# MCU.net
KiCad netlist of a schematic drawn in Altium Designer
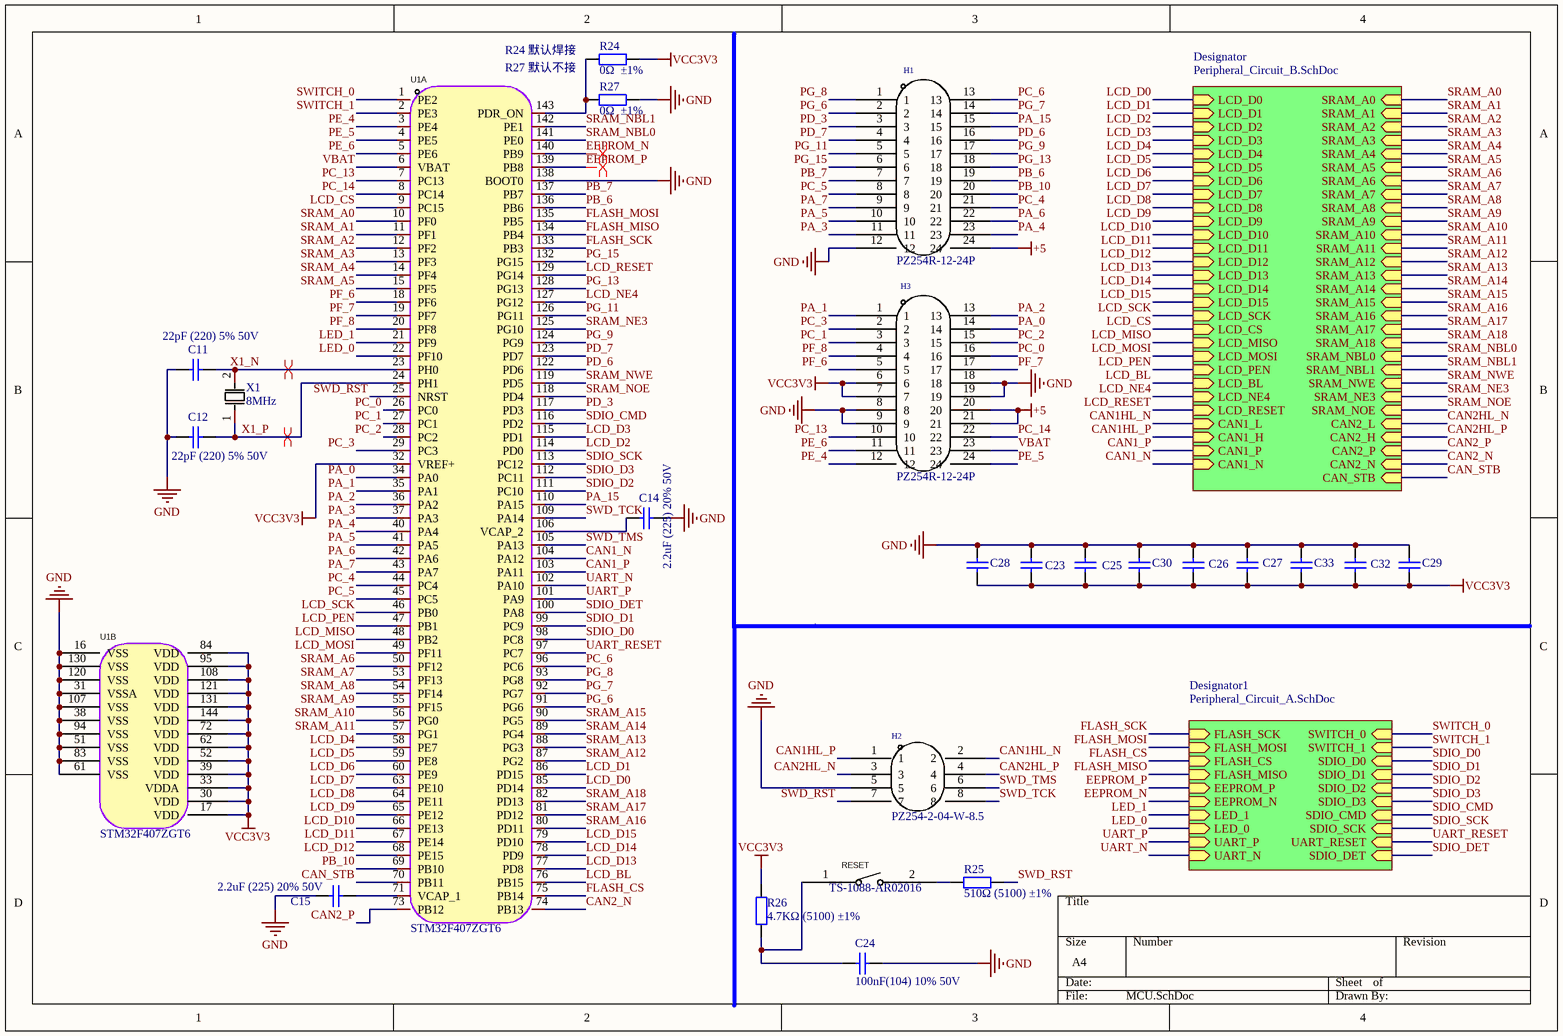
[diagram p0: MCU.SchDoc]

(export (version "E")
  (design (tool "Eeschema 10.0.6"))
  (components
    (comp (ref "C11")
      (value "22pF (220) 5% 50V")
      (footprint "0805_C")
      (description "贴片电容")
      (libsource (lib "Miscellaneous Devices LC") (part "0805 22pF (220) 5% 50V"))
    )
    (comp (ref "C12")
      (value "22pF (220) 5% 50V")
      (footprint "0805_C")
      (description "贴片电容")
      (libsource (lib "Miscellaneous Devices LC") (part "0805 22pF (220) 5% 50V"))
    )
    (comp (ref "C14")
      (value "2.2uF (225) 20% 50V")
      (footprint "0805_C")
      (description "贴片电容")
      (libsource (lib "Miscellaneous Devices LC") (part "0805 2.2uF (225) 20% 50V"))
    )
    (comp (ref "C15")
      (value "2.2uF (225) 20% 50V")
      (footprint "0805_C")
      (description "贴片电容")
      (libsource (lib "Miscellaneous Devices LC") (part "0805 2.2uF (225) 20% 50V"))
    )
    (comp (ref "C23")
      (value "100nF(104) 10% 50V")
      (footprint "0805_C")
      (description "贴片电容")
      (libsource (lib "Miscellaneous Devices LC") (part "0805 100nF(104) 10% 50V"))
    )
    (comp (ref "C24")
      (value "100nF(104) 10% 50V")
      (footprint "0805_C")
      (description "贴片电容")
      (libsource (lib "Miscellaneous Devices LC") (part "0805 100nF(104) 10% 50V"))
    )
    (comp (ref "C25")
      (value "100nF(104) 10% 50V")
      (footprint "0805_C")
      (description "贴片电容")
      (libsource (lib "Miscellaneous Devices LC") (part "0805 100nF(104) 10% 50V"))
    )
    (comp (ref "C26")
      (value "100nF(104) 10% 50V")
      (footprint "0805_C")
      (description "贴片电容")
      (libsource (lib "Miscellaneous Devices LC") (part "0805 100nF(104) 10% 50V"))
    )
    (comp (ref "C27")
      (value "100nF(104) 10% 50V")
      (footprint "0805_C")
      (description "贴片电容")
      (libsource (lib "Miscellaneous Devices LC") (part "0805 100nF(104) 10% 50V"))
    )
    (comp (ref "C28")
      (value "100nF(104) 10% 50V")
      (footprint "0805_C")
      (description "贴片电容")
      (libsource (lib "Miscellaneous Devices LC") (part "0805 100nF(104) 10% 50V"))
    )
    (comp (ref "C29")
      (value "100nF(104) 10% 50V")
      (footprint "0805_C")
      (description "贴片电容")
      (libsource (lib "Miscellaneous Devices LC") (part "0805 100nF(104) 10% 50V"))
    )
    (comp (ref "C30")
      (value "100nF(104) 10% 50V")
      (footprint "0805_C")
      (description "贴片电容")
      (libsource (lib "Miscellaneous Devices LC") (part "0805 100nF(104) 10% 50V"))
    )
    (comp (ref "C32")
      (value "100nF(104) 10% 50V")
      (footprint "0805_C")
      (description "贴片电容")
      (libsource (lib "Miscellaneous Devices LC") (part "0805 100nF(104) 10% 50V"))
    )
    (comp (ref "C33")
      (value "100nF(104) 10% 50V")
      (footprint "0805_C")
      (description "贴片电容")
      (libsource (lib "Miscellaneous Devices LC") (part "0805 100nF(104) 10% 50V"))
    )
    (comp (ref "H1")
      (value "PZ254R-12-24P")
      (footprint "PZ254R-12-24P")
      (description "2X12P 弯针")
      (fields (field (name "MANUFACTURER") "XFCN(兴飞)") (field (name "NAME") "PZ254R-12-24P"))
      (libsource (lib "EXTRA") (part "PZ254R-12-24P"))
    )
    (comp (ref "H2")
      (value "PZ254-2-04-W-8.5")
      (footprint "PZ254-2-04-W-8.5")
      (description "2.54mm 2x4p 弯针")
      (fields (field (name "MANUFACTURER") "HCTL(华灿天禄)"))
      (libsource (lib "EXTRA") (part "PZ254-2-04-W-8.5"))
    )
    (comp (ref "H3")
      (value "PZ254R-12-24P")
      (footprint "PZ254R-12-24P")
      (description "2X12P 弯针")
      (fields (field (name "MANUFACTURER") "XFCN(兴飞)") (field (name "NAME") "PZ254R-12-24P"))
      (libsource (lib "EXTRA") (part "PZ254R-12-24P"))
    )
    (comp (ref "R24")
      (value "0Ω  ±1%")
      (footprint "0805_R")
      (description "贴片电阻")
      (libsource (lib "Miscellaneous Devices LC") (part "0805 510Ω (5100) 1%"))
    )
    (comp (ref "R25")
      (value "510Ω (5100) ±1%")
      (footprint "0805_R")
      (description "贴片电阻")
      (libsource (lib "Miscellaneous Devices LC") (part "0805 510Ω (5100) 1%"))
    )
    (comp (ref "R26")
      (value "4.7KΩ (5100) ±1%")
      (footprint "0805_R")
      (description "贴片电阻")
      (libsource (lib "") (part "0805 510Ω (5100) 1%_1"))
    )
    (comp (ref "R27")
      (value "0Ω  ±1%")
      (footprint "0805_R")
      (description "贴片电阻")
      (libsource (lib "Miscellaneous Devices LC") (part "0805 510Ω (5100) 1%"))
    )
    (comp (ref "RESET")
      (value "TS-1088-AR02016")
      (footprint "SW-SMD_L3.9-W3.0-P4.45")
      (description "轻触开关")
      (fields (field (name "MANUFACTURER") "XUNPU(讯普)"))
      (libsource (lib "EXTRA") (part "TS-1088-AR02016"))
    )
    (comp (ref "U1")
      (value "STM32F407ZGT6")
      (footprint "LQFP-144_L20.0-W20.0-P0.50-LS22.0-BL")
      (description "STM32F407ZGT6MCU")
      (fields (field (name "MANUFACTURER") "ST(意法半导体)"))
      (libsource (lib "EXTRA") (part "STM32F407ZGT6"))
    )
    (comp (ref "X1")
      (value "8MHZ")
      (footprint "CRYSTAL-SMD_L5.0-W3.2")
      (description "贴片晶振")
      (fields
        (field (name "MANUFACTURER") "YXC(扬兴晶振)")
        (field (name "MANUFACTURER PART") "X50328MSB2GI")
        (field (name "NAME") "8MHz")
      )
      (libsource (lib "EXTRA") (part "X50328MSB2GI"))
    )
  )
  (nets
    (net (code "1") (name "+5") (class "Default")
      (node (ref "H1") (pin "24") (pinfunction "24_24") (pintype "passive"))
      (node (ref "H3") (pin "20") (pinfunction "20_20") (pintype "passive"))
      (node (ref "H3") (pin "21") (pinfunction "21_21") (pintype "passive"))
    )
    (net (code "2") (name "/CAN1HL_N") (class "Default")
      (node (ref "H2") (pin "2") (pinfunction "2_2") (pintype "passive"))
    )
    (net (code "3") (name "/CAN1HL_P") (class "Default")
      (node (ref "H2") (pin "1") (pinfunction "1_1") (pintype "passive"))
    )
    (net (code "4") (name "/CAN1_N") (class "Default")
      (node (ref "U1") (pin "104") (pinfunction "PA12_104") (pintype "passive"))
    )
    (net (code "5") (name "/CAN1_P") (class "Default")
      (node (ref "U1") (pin "103") (pinfunction "PA11_103") (pintype "passive"))
    )
    (net (code "6") (name "/CAN2HL_N") (class "Default")
      (node (ref "H2") (pin "3") (pinfunction "3_3") (pintype "passive"))
    )
    (net (code "7") (name "/CAN2HL_P") (class "Default")
      (node (ref "H2") (pin "4") (pinfunction "4_4") (pintype "passive"))
    )
    (net (code "8") (name "/CAN2_N") (class "Default")
      (node (ref "U1") (pin "74") (pinfunction "PB13_74") (pintype "passive"))
    )
    (net (code "9") (name "/CAN2_P") (class "Default")
      (node (ref "U1") (pin "73") (pinfunction "PB12_73") (pintype "passive"))
    )
    (net (code "10") (name "/CAN_STB") (class "Default")
      (node (ref "U1") (pin "70") (pinfunction "PB11_70") (pintype "passive"))
    )
    (net (code "11") (name "/EEPROM_N") (class "Default")
      (node (ref "U1") (pin "140") (pinfunction "PB9_140") (pintype "passive"))
    )
    (net (code "12") (name "/EEPROM_P") (class "Default")
      (node (ref "U1") (pin "139") (pinfunction "PB8_139") (pintype "passive"))
    )
    (net (code "13") (name "/FLASH_CS") (class "Default")
      (node (ref "U1") (pin "75") (pinfunction "PB14_75") (pintype "passive"))
    )
    (net (code "14") (name "/FLASH_MISO") (class "Default")
      (node (ref "U1") (pin "134") (pinfunction "PB4_134") (pintype "passive"))
    )
    (net (code "15") (name "/FLASH_MOSI") (class "Default")
      (node (ref "U1") (pin "135") (pinfunction "PB5_135") (pintype "passive"))
    )
    (net (code "16") (name "/FLASH_SCK") (class "Default")
      (node (ref "U1") (pin "133") (pinfunction "PB3_133") (pintype "passive"))
    )
    (net (code "17") (name "/LCD_BL") (class "Default")
      (node (ref "U1") (pin "76") (pinfunction "PB15_76") (pintype "passive"))
    )
    (net (code "18") (name "/LCD_CS") (class "Default")
      (node (ref "U1") (pin "9") (pinfunction "PC15_9") (pintype "passive"))
    )
    (net (code "19") (name "/LCD_D0") (class "Default")
      (node (ref "U1") (pin "85") (pinfunction "PD14_85") (pintype "passive"))
    )
    (net (code "20") (name "/LCD_D1") (class "Default")
      (node (ref "U1") (pin "86") (pinfunction "PD15_86") (pintype "passive"))
    )
    (net (code "21") (name "/LCD_D2") (class "Default")
      (node (ref "U1") (pin "114") (pinfunction "PD0_114") (pintype "passive"))
    )
    (net (code "22") (name "/LCD_D3") (class "Default")
      (node (ref "U1") (pin "115") (pinfunction "PD1_115") (pintype "passive"))
    )
    (net (code "23") (name "/LCD_D4") (class "Default")
      (node (ref "U1") (pin "58") (pinfunction "PE7_58") (pintype "passive"))
    )
    (net (code "24") (name "/LCD_D5") (class "Default")
      (node (ref "U1") (pin "59") (pinfunction "PE8_59") (pintype "passive"))
    )
    (net (code "25") (name "/LCD_D6") (class "Default")
      (node (ref "U1") (pin "60") (pinfunction "PE9_60") (pintype "passive"))
    )
    (net (code "26") (name "/LCD_D7") (class "Default")
      (node (ref "U1") (pin "63") (pinfunction "PE10_63") (pintype "passive"))
    )
    (net (code "27") (name "/LCD_D8") (class "Default")
      (node (ref "U1") (pin "64") (pinfunction "PE11_64") (pintype "passive"))
    )
    (net (code "28") (name "/LCD_D9") (class "Default")
      (node (ref "U1") (pin "65") (pinfunction "PE12_65") (pintype "passive"))
    )
    (net (code "29") (name "/LCD_D10") (class "Default")
      (node (ref "U1") (pin "66") (pinfunction "PE13_66") (pintype "passive"))
    )
    (net (code "30") (name "/LCD_D11") (class "Default")
      (node (ref "U1") (pin "67") (pinfunction "PE14_67") (pintype "passive"))
    )
    (net (code "31") (name "/LCD_D12") (class "Default")
      (node (ref "U1") (pin "68") (pinfunction "PE15_68") (pintype "passive"))
    )
    (net (code "32") (name "/LCD_D13") (class "Default")
      (node (ref "U1") (pin "77") (pinfunction "PD8_77") (pintype "passive"))
    )
    (net (code "33") (name "/LCD_D14") (class "Default")
      (node (ref "U1") (pin "78") (pinfunction "PD9_78") (pintype "passive"))
    )
    (net (code "34") (name "/LCD_D15") (class "Default")
      (node (ref "U1") (pin "79") (pinfunction "PD10_79") (pintype "passive"))
    )
    (net (code "35") (name "/LCD_MISO") (class "Default")
      (node (ref "U1") (pin "48") (pinfunction "PB2_48") (pintype "passive"))
    )
    (net (code "36") (name "/LCD_MOSI") (class "Default")
      (node (ref "U1") (pin "49") (pinfunction "PF11_49") (pintype "passive"))
    )
    (net (code "37") (name "/LCD_NE4") (class "Default")
      (node (ref "U1") (pin "127") (pinfunction "PG12_127") (pintype "passive"))
    )
    (net (code "38") (name "/LCD_PEN") (class "Default")
      (node (ref "U1") (pin "47") (pinfunction "PB1_47") (pintype "passive"))
    )
    (net (code "39") (name "/LCD_RESET") (class "Default")
      (node (ref "U1") (pin "129") (pinfunction "PG14_129") (pintype "passive"))
    )
    (net (code "40") (name "/LCD_SCK") (class "Default")
      (node (ref "U1") (pin "46") (pinfunction "PB0_46") (pintype "passive"))
    )
    (net (code "41") (name "/LED_0") (class "Default")
      (node (ref "U1") (pin "22") (pinfunction "PF10_22") (pintype "passive"))
    )
    (net (code "42") (name "/LED_1") (class "Default")
      (node (ref "U1") (pin "21") (pinfunction "PF9_21") (pintype "passive"))
    )
    (net (code "43") (name "/PA_0") (class "Default")
      (node (ref "H3") (pin "14") (pinfunction "14_14") (pintype "passive"))
      (node (ref "U1") (pin "34") (pinfunction "PA0_34") (pintype "passive"))
    )
    (net (code "44") (name "/PA_1") (class "Default")
      (node (ref "H3") (pin "1") (pinfunction "1_1") (pintype "passive"))
      (node (ref "U1") (pin "35") (pinfunction "PA1_35") (pintype "passive"))
    )
    (net (code "45") (name "/PA_2") (class "Default")
      (node (ref "H3") (pin "13") (pinfunction "13_13") (pintype "passive"))
      (node (ref "U1") (pin "36") (pinfunction "PA2_36") (pintype "passive"))
    )
    (net (code "46") (name "/PA_3") (class "Default")
      (node (ref "H1") (pin "11") (pinfunction "11_11") (pintype "passive"))
      (node (ref "U1") (pin "37") (pinfunction "PA3_37") (pintype "passive"))
    )
    (net (code "47") (name "/PA_4") (class "Default")
      (node (ref "H1") (pin "23") (pinfunction "23_23") (pintype "passive"))
      (node (ref "U1") (pin "40") (pinfunction "PA4_40") (pintype "passive"))
    )
    (net (code "48") (name "/PA_5") (class "Default")
      (node (ref "H1") (pin "10") (pinfunction "10_10") (pintype "passive"))
      (node (ref "U1") (pin "41") (pinfunction "PA5_41") (pintype "passive"))
    )
    (net (code "49") (name "/PA_6") (class "Default")
      (node (ref "H1") (pin "22") (pinfunction "22_22") (pintype "passive"))
      (node (ref "U1") (pin "42") (pinfunction "PA6_42") (pintype "passive"))
    )
    (net (code "50") (name "/PA_7") (class "Default")
      (node (ref "H1") (pin "9") (pinfunction "9_9") (pintype "passive"))
      (node (ref "U1") (pin "43") (pinfunction "PA7_43") (pintype "passive"))
    )
    (net (code "51") (name "/PA_15") (class "Default")
      (node (ref "H1") (pin "15") (pinfunction "15_15") (pintype "passive"))
      (node (ref "U1") (pin "110") (pinfunction "PA15_110") (pintype "passive"))
    )
    (net (code "52") (name "/PB_6") (class "Default")
      (node (ref "H1") (pin "19") (pinfunction "19_19") (pintype "passive"))
      (node (ref "U1") (pin "136") (pinfunction "PB6_136") (pintype "passive"))
    )
    (net (code "53") (name "/PB_7") (class "Default")
      (node (ref "H1") (pin "7") (pinfunction "7_7") (pintype "passive"))
      (node (ref "U1") (pin "137") (pinfunction "PB7_137") (pintype "passive"))
    )
    (net (code "54") (name "/PB_10") (class "Default")
      (node (ref "H1") (pin "20") (pinfunction "20_20") (pintype "passive"))
      (node (ref "U1") (pin "69") (pinfunction "PB10_69") (pintype "passive"))
    )
    (net (code "55") (name "/PC_0") (class "Default")
      (node (ref "H3") (pin "16") (pinfunction "16_16") (pintype "passive"))
      (node (ref "U1") (pin "26") (pinfunction "PC0_26") (pintype "passive"))
    )
    (net (code "56") (name "/PC_1") (class "Default")
      (node (ref "H3") (pin "3") (pinfunction "3_3") (pintype "passive"))
      (node (ref "U1") (pin "27") (pinfunction "PC1_27") (pintype "passive"))
    )
    (net (code "57") (name "/PC_2") (class "Default")
      (node (ref "H3") (pin "15") (pinfunction "15_15") (pintype "passive"))
      (node (ref "U1") (pin "28") (pinfunction "PC2_28") (pintype "passive"))
    )
    (net (code "58") (name "/PC_3") (class "Default")
      (node (ref "H3") (pin "2") (pinfunction "2_2") (pintype "passive"))
      (node (ref "U1") (pin "29") (pinfunction "PC3_29") (pintype "passive"))
    )
    (net (code "59") (name "/PC_4") (class "Default")
      (node (ref "H1") (pin "21") (pinfunction "21_21") (pintype "passive"))
      (node (ref "U1") (pin "44") (pinfunction "PC4_44") (pintype "passive"))
    )
    (net (code "60") (name "/PC_5") (class "Default")
      (node (ref "H1") (pin "8") (pinfunction "8_8") (pintype "passive"))
      (node (ref "U1") (pin "45") (pinfunction "PC5_45") (pintype "passive"))
    )
    (net (code "61") (name "/PC_6") (class "Default")
      (node (ref "H1") (pin "13") (pinfunction "13_13") (pintype "passive"))
      (node (ref "U1") (pin "96") (pinfunction "PC6_96") (pintype "passive"))
    )
    (net (code "62") (name "/PC_13") (class "Default")
      (node (ref "H3") (pin "10") (pinfunction "10_10") (pintype "passive"))
      (node (ref "U1") (pin "7") (pinfunction "PC13_7") (pintype "passive"))
    )
    (net (code "63") (name "/PC_14") (class "Default")
      (node (ref "H3") (pin "22") (pinfunction "22_22") (pintype "passive"))
      (node (ref "U1") (pin "8") (pinfunction "PC14_8") (pintype "passive"))
    )
    (net (code "64") (name "/PD_3") (class "Default")
      (node (ref "H1") (pin "3") (pinfunction "3_3") (pintype "passive"))
      (node (ref "U1") (pin "117") (pinfunction "PD3_117") (pintype "passive"))
    )
    (net (code "65") (name "/PD_6") (class "Default")
      (node (ref "H1") (pin "16") (pinfunction "16_16") (pintype "passive"))
      (node (ref "U1") (pin "122") (pinfunction "PD6_122") (pintype "passive"))
    )
    (net (code "66") (name "/PD_7") (class "Default")
      (node (ref "H1") (pin "4") (pinfunction "4_4") (pintype "passive"))
      (node (ref "U1") (pin "123") (pinfunction "PD7_123") (pintype "passive"))
    )
    (net (code "67") (name "/PE_4") (class "Default")
      (node (ref "H3") (pin "12") (pinfunction "12_12") (pintype "passive"))
      (node (ref "U1") (pin "3") (pinfunction "PE4_3") (pintype "passive"))
    )
    (net (code "68") (name "/PE_5") (class "Default")
      (node (ref "H3") (pin "24") (pinfunction "24_24") (pintype "passive"))
      (node (ref "U1") (pin "4") (pinfunction "PE5_4") (pintype "passive"))
    )
    (net (code "69") (name "/PE_6") (class "Default")
      (node (ref "H3") (pin "11") (pinfunction "11_11") (pintype "passive"))
      (node (ref "U1") (pin "5") (pinfunction "PE6_5") (pintype "passive"))
    )
    (net (code "70") (name "/PF_6") (class "Default")
      (node (ref "H3") (pin "5") (pinfunction "5_5") (pintype "passive"))
      (node (ref "U1") (pin "18") (pinfunction "PF6_18") (pintype "passive"))
    )
    (net (code "71") (name "/PF_7") (class "Default")
      (node (ref "H3") (pin "17") (pinfunction "17_17") (pintype "passive"))
      (node (ref "U1") (pin "19") (pinfunction "PF7_19") (pintype "passive"))
    )
    (net (code "72") (name "/PF_8") (class "Default")
      (node (ref "H3") (pin "4") (pinfunction "4_4") (pintype "passive"))
      (node (ref "U1") (pin "20") (pinfunction "PF8_20") (pintype "passive"))
    )
    (net (code "73") (name "/PG_6") (class "Default")
      (node (ref "H1") (pin "2") (pinfunction "2_2") (pintype "passive"))
      (node (ref "U1") (pin "91") (pinfunction "PG6_91") (pintype "passive"))
    )
    (net (code "74") (name "/PG_7") (class "Default")
      (node (ref "H1") (pin "14") (pinfunction "14_14") (pintype "passive"))
      (node (ref "U1") (pin "92") (pinfunction "PG7_92") (pintype "passive"))
    )
    (net (code "75") (name "/PG_8") (class "Default")
      (node (ref "H1") (pin "1") (pinfunction "1_1") (pintype "passive"))
      (node (ref "U1") (pin "93") (pinfunction "PG8_93") (pintype "passive"))
    )
    (net (code "76") (name "/PG_9") (class "Default")
      (node (ref "H1") (pin "17") (pinfunction "17_17") (pintype "passive"))
      (node (ref "U1") (pin "124") (pinfunction "PG9_124") (pintype "passive"))
    )
    (net (code "77") (name "/PG_11") (class "Default")
      (node (ref "H1") (pin "5") (pinfunction "5_5") (pintype "passive"))
      (node (ref "U1") (pin "126") (pinfunction "PG11_126") (pintype "passive"))
    )
    (net (code "78") (name "/PG_13") (class "Default")
      (node (ref "H1") (pin "18") (pinfunction "18_18") (pintype "passive"))
      (node (ref "U1") (pin "128") (pinfunction "PG13_128") (pintype "passive"))
    )
    (net (code "79") (name "/PG_15") (class "Default")
      (node (ref "H1") (pin "6") (pinfunction "6_6") (pintype "passive"))
      (node (ref "U1") (pin "132") (pinfunction "PG15_132") (pintype "passive"))
    )
    (net (code "80") (name "/SDIO_CMD") (class "Default")
      (node (ref "U1") (pin "116") (pinfunction "PD2_116") (pintype "passive"))
    )
    (net (code "81") (name "/SDIO_D0") (class "Default")
      (node (ref "U1") (pin "98") (pinfunction "PC8_98") (pintype "passive"))
    )
    (net (code "82") (name "/SDIO_D1") (class "Default")
      (node (ref "U1") (pin "99") (pinfunction "PC9_99") (pintype "passive"))
    )
    (net (code "83") (name "/SDIO_D2") (class "Default")
      (node (ref "U1") (pin "111") (pinfunction "PC10_111") (pintype "passive"))
    )
    (net (code "84") (name "/SDIO_D3") (class "Default")
      (node (ref "U1") (pin "112") (pinfunction "PC11_112") (pintype "passive"))
    )
    (net (code "85") (name "/SDIO_DET") (class "Default")
      (node (ref "U1") (pin "100") (pinfunction "PA8_100") (pintype "passive"))
    )
    (net (code "86") (name "/SDIO_SCK") (class "Default")
      (node (ref "U1") (pin "113") (pinfunction "PC12_113") (pintype "passive"))
    )
    (net (code "87") (name "/SRAM_A0") (class "Default")
      (node (ref "U1") (pin "10") (pinfunction "PF0_10") (pintype "passive"))
    )
    (net (code "88") (name "/SRAM_A1") (class "Default")
      (node (ref "U1") (pin "11") (pinfunction "PF1_11") (pintype "passive"))
    )
    (net (code "89") (name "/SRAM_A2") (class "Default")
      (node (ref "U1") (pin "12") (pinfunction "PF2_12") (pintype "passive"))
    )
    (net (code "90") (name "/SRAM_A3") (class "Default")
      (node (ref "U1") (pin "13") (pinfunction "PF3_13") (pintype "passive"))
    )
    (net (code "91") (name "/SRAM_A4") (class "Default")
      (node (ref "U1") (pin "14") (pinfunction "PF4_14") (pintype "passive"))
    )
    (net (code "92") (name "/SRAM_A5") (class "Default")
      (node (ref "U1") (pin "15") (pinfunction "PF5_15") (pintype "passive"))
    )
    (net (code "93") (name "/SRAM_A6") (class "Default")
      (node (ref "U1") (pin "50") (pinfunction "PF12_50") (pintype "passive"))
    )
    (net (code "94") (name "/SRAM_A7") (class "Default")
      (node (ref "U1") (pin "53") (pinfunction "PF13_53") (pintype "passive"))
    )
    (net (code "95") (name "/SRAM_A8") (class "Default")
      (node (ref "U1") (pin "54") (pinfunction "PF14_54") (pintype "passive"))
    )
    (net (code "96") (name "/SRAM_A9") (class "Default")
      (node (ref "U1") (pin "55") (pinfunction "PF15_55") (pintype "passive"))
    )
    (net (code "97") (name "/SRAM_A10") (class "Default")
      (node (ref "U1") (pin "56") (pinfunction "PG0_56") (pintype "passive"))
    )
    (net (code "98") (name "/SRAM_A11") (class "Default")
      (node (ref "U1") (pin "57") (pinfunction "PG1_57") (pintype "passive"))
    )
    (net (code "99") (name "/SRAM_A12") (class "Default")
      (node (ref "U1") (pin "87") (pinfunction "PG2_87") (pintype "passive"))
    )
    (net (code "100") (name "/SRAM_A13") (class "Default")
      (node (ref "U1") (pin "88") (pinfunction "PG3_88") (pintype "passive"))
    )
    (net (code "101") (name "/SRAM_A14") (class "Default")
      (node (ref "U1") (pin "89") (pinfunction "PG4_89") (pintype "passive"))
    )
    (net (code "102") (name "/SRAM_A15") (class "Default")
      (node (ref "U1") (pin "90") (pinfunction "PG5_90") (pintype "passive"))
    )
    (net (code "103") (name "/SRAM_A16") (class "Default")
      (node (ref "U1") (pin "80") (pinfunction "PD11_80") (pintype "passive"))
    )
    (net (code "104") (name "/SRAM_A17") (class "Default")
      (node (ref "U1") (pin "81") (pinfunction "PD12_81") (pintype "passive"))
    )
    (net (code "105") (name "/SRAM_A18") (class "Default")
      (node (ref "U1") (pin "82") (pinfunction "PD13_82") (pintype "passive"))
    )
    (net (code "106") (name "/SRAM_NBL0") (class "Default")
      (node (ref "U1") (pin "141") (pinfunction "PE0_141") (pintype "passive"))
    )
    (net (code "107") (name "/SRAM_NBL1") (class "Default")
      (node (ref "U1") (pin "142") (pinfunction "PE1_142") (pintype "passive"))
    )
    (net (code "108") (name "/SRAM_NE3") (class "Default")
      (node (ref "U1") (pin "125") (pinfunction "PG10_125") (pintype "passive"))
    )
    (net (code "109") (name "/SRAM_NOE") (class "Default")
      (node (ref "U1") (pin "118") (pinfunction "PD4_118") (pintype "passive"))
    )
    (net (code "110") (name "/SRAM_NWE") (class "Default")
      (node (ref "U1") (pin "119") (pinfunction "PD5_119") (pintype "passive"))
    )
    (net (code "111") (name "/SWD_RST") (class "Default")
      (node (ref "H2") (pin "7") (pinfunction "7_7") (pintype "passive"))
      (node (ref "R25") (pin "2") (pinfunction "2_2") (pintype "passive"))
      (node (ref "U1") (pin "25") (pinfunction "NRST_25") (pintype "passive"))
    )
    (net (code "112") (name "/SWD_TCK") (class "Default")
      (node (ref "H2") (pin "8") (pinfunction "8_8") (pintype "passive"))
      (node (ref "U1") (pin "109") (pinfunction "PA14_109") (pintype "passive"))
    )
    (net (code "113") (name "/SWD_TMS") (class "Default")
      (node (ref "H2") (pin "6") (pinfunction "6_6") (pintype "passive"))
      (node (ref "U1") (pin "105") (pinfunction "PA13_105") (pintype "passive"))
    )
    (net (code "114") (name "/SWITCH_0") (class "Default")
      (node (ref "U1") (pin "1") (pinfunction "PE2_1") (pintype "passive"))
    )
    (net (code "115") (name "/SWITCH_1") (class "Default")
      (node (ref "U1") (pin "2") (pinfunction "PE3_2") (pintype "passive"))
    )
    (net (code "116") (name "/UART_N") (class "Default")
      (node (ref "U1") (pin "102") (pinfunction "PA10_102") (pintype "passive"))
    )
    (net (code "117") (name "/UART_P") (class "Default")
      (node (ref "U1") (pin "101") (pinfunction "PA9_101") (pintype "passive"))
    )
    (net (code "118") (name "/UART_RESET") (class "Default")
      (node (ref "U1") (pin "97") (pinfunction "PC7_97") (pintype "passive"))
    )
    (net (code "119") (name "/VBAT") (class "Default")
      (node (ref "H3") (pin "23") (pinfunction "23_23") (pintype "passive"))
      (node (ref "U1") (pin "6") (pinfunction "VBAT_6") (pintype "passive"))
    )
    (net (code "120") (name "/X1_N") (class "Default")
      (node (ref "C11") (pin "2") (pinfunction "2_2") (pintype "passive"))
      (node (ref "U1") (pin "23") (pinfunction "PH0_23") (pintype "passive"))
      (node (ref "X1") (pin "2") (pinfunction "OSC2_2") (pintype "passive"))
    )
    (net (code "121") (name "/X1_P") (class "Default")
      (node (ref "C12") (pin "2") (pinfunction "2_2") (pintype "passive"))
      (node (ref "U1") (pin "24") (pinfunction "PH1_24") (pintype "passive"))
      (node (ref "X1") (pin "1") (pinfunction "OSC1_1") (pintype "passive"))
    )
    (net (code "122") (name "GND") (class "Default")
      (node (ref "C11") (pin "1") (pinfunction "1_1") (pintype "passive"))
      (node (ref "C12") (pin "1") (pinfunction "1_1") (pintype "passive"))
      (node (ref "C14") (pin "2") (pinfunction "2_2") (pintype "passive"))
      (node (ref "C15") (pin "1") (pinfunction "1_1") (pintype "passive"))
      (node (ref "C23") (pin "2") (pinfunction "2_2") (pintype "passive"))
      (node (ref "C24") (pin "1") (pinfunction "1_1") (pintype "passive"))
      (node (ref "C25") (pin "2") (pinfunction "2_2") (pintype "passive"))
      (node (ref "C26") (pin "2") (pinfunction "2_2") (pintype "passive"))
      (node (ref "C27") (pin "2") (pinfunction "2_2") (pintype "passive"))
      (node (ref "C28") (pin "1") (pinfunction "1_1") (pintype "passive"))
      (node (ref "C29") (pin "1") (pinfunction "1_1") (pintype "passive"))
      (node (ref "C30") (pin "1") (pinfunction "1_1") (pintype "passive"))
      (node (ref "C32") (pin "2") (pinfunction "2_2") (pintype "passive"))
      (node (ref "C33") (pin "1") (pinfunction "1_1") (pintype "passive"))
      (node (ref "H1") (pin "12") (pinfunction "12_12") (pintype "passive"))
      (node (ref "H2") (pin "5") (pinfunction "5_5") (pintype "passive"))
      (node (ref "H3") (pin "18") (pinfunction "18_18") (pintype "passive"))
      (node (ref "H3") (pin "19") (pinfunction "19_19") (pintype "passive"))
      (node (ref "H3") (pin "8") (pinfunction "8_8") (pintype "passive"))
      (node (ref "H3") (pin "9") (pinfunction "9_9") (pintype "passive"))
      (node (ref "R27") (pin "2") (pinfunction "2_2") (pintype "passive"))
      (node (ref "U1") (pin "107") (pinfunction "VSS_107") (pintype "passive"))
      (node (ref "U1") (pin "120") (pinfunction "VSS_120") (pintype "passive"))
      (node (ref "U1") (pin "130") (pinfunction "VSS_130") (pintype "passive"))
      (node (ref "U1") (pin "138") (pinfunction "BOOT0_138") (pintype "passive"))
      (node (ref "U1") (pin "16") (pinfunction "VSS_16") (pintype "passive"))
      (node (ref "U1") (pin "31") (pinfunction "VSSA_31") (pintype "passive"))
      (node (ref "U1") (pin "38") (pinfunction "VSS_38") (pintype "passive"))
      (node (ref "U1") (pin "51") (pinfunction "VSS_51") (pintype "passive"))
      (node (ref "U1") (pin "61") (pinfunction "VSS_61") (pintype "passive"))
      (node (ref "U1") (pin "83") (pinfunction "VSS_83") (pintype "passive"))
      (node (ref "U1") (pin "94") (pinfunction "VSS_94") (pintype "passive"))
    )
    (net (code "123") (name "Net-(C24-Pad2)") (class "Default")
      (node (ref "C24") (pin "2") (pinfunction "2_2") (pintype "passive"))
      (node (ref "R26") (pin "2") (pinfunction "2_2") (pintype "passive"))
      (node (ref "RESET") (pin "1") (pinfunction "1_1") (pintype "passive"))
    )
    (net (code "124") (name "Net-(R25-Pad1)") (class "Default")
      (node (ref "R25") (pin "1") (pinfunction "1_1") (pintype "passive"))
      (node (ref "RESET") (pin "2") (pinfunction "2_2") (pintype "passive"))
    )
    (net (code "125") (name "Net-(U1A-PDR_ON)") (class "Default")
      (node (ref "R24") (pin "1") (pinfunction "1_1") (pintype "passive"))
      (node (ref "R27") (pin "1") (pinfunction "1_1") (pintype "passive"))
      (node (ref "U1") (pin "143") (pinfunction "PDR_ON_143") (pintype "passive"))
    )
    (net (code "126") (name "Net-(U1A-VCAP_1)") (class "Default")
      (node (ref "C15") (pin "2") (pinfunction "2_2") (pintype "passive"))
      (node (ref "U1") (pin "71") (pinfunction "VCAP_1_71") (pintype "passive"))
    )
    (net (code "127") (name "Net-(U1A-VCAP_2)") (class "Default")
      (node (ref "C14") (pin "1") (pinfunction "1_1") (pintype "passive"))
      (node (ref "U1") (pin "106") (pinfunction "VCAP_2_106") (pintype "passive"))
    )
    (net (code "128") (name "VCC3V3") (class "Default")
      (node (ref "C23") (pin "1") (pinfunction "1_1") (pintype "passive"))
      (node (ref "C25") (pin "1") (pinfunction "1_1") (pintype "passive"))
      (node (ref "C26") (pin "1") (pinfunction "1_1") (pintype "passive"))
      (node (ref "C27") (pin "1") (pinfunction "1_1") (pintype "passive"))
      (node (ref "C28") (pin "2") (pinfunction "2_2") (pintype "passive"))
      (node (ref "C29") (pin "2") (pinfunction "2_2") (pintype "passive"))
      (node (ref "C30") (pin "2") (pinfunction "2_2") (pintype "passive"))
      (node (ref "C32") (pin "1") (pinfunction "1_1") (pintype "passive"))
      (node (ref "C33") (pin "2") (pinfunction "2_2") (pintype "passive"))
      (node (ref "H3") (pin "6") (pinfunction "6_6") (pintype "passive"))
      (node (ref "H3") (pin "7") (pinfunction "7_7") (pintype "passive"))
      (node (ref "R24") (pin "2") (pinfunction "2_2") (pintype "passive"))
      (node (ref "R26") (pin "1") (pinfunction "1_1") (pintype "passive"))
      (node (ref "U1") (pin "108") (pinfunction "VDD_108") (pintype "passive"))
      (node (ref "U1") (pin "121") (pinfunction "VDD_121") (pintype "passive"))
      (node (ref "U1") (pin "131") (pinfunction "VDD_131") (pintype "passive"))
      (node (ref "U1") (pin "144") (pinfunction "VDD_144") (pintype "passive"))
      (node (ref "U1") (pin "17") (pinfunction "VDD_17") (pintype "passive"))
      (node (ref "U1") (pin "30") (pinfunction "VDD_30") (pintype "passive"))
      (node (ref "U1") (pin "32") (pinfunction "VREF+_32") (pintype "passive"))
      (node (ref "U1") (pin "33") (pinfunction "VDDA_33") (pintype "passive"))
      (node (ref "U1") (pin "39") (pinfunction "VDD_39") (pintype "passive"))
      (node (ref "U1") (pin "52") (pinfunction "VDD_52") (pintype "passive"))
      (node (ref "U1") (pin "62") (pinfunction "VDD_62") (pintype "passive"))
      (node (ref "U1") (pin "72") (pinfunction "VDD_72") (pintype "passive"))
      (node (ref "U1") (pin "84") (pinfunction "VDD_84") (pintype "passive"))
      (node (ref "U1") (pin "95") (pinfunction "VDD_95") (pintype "passive"))
    )
  )
)
